# CANreader-FT.net
KiCad netlist of a schematic drawn in EAGLE
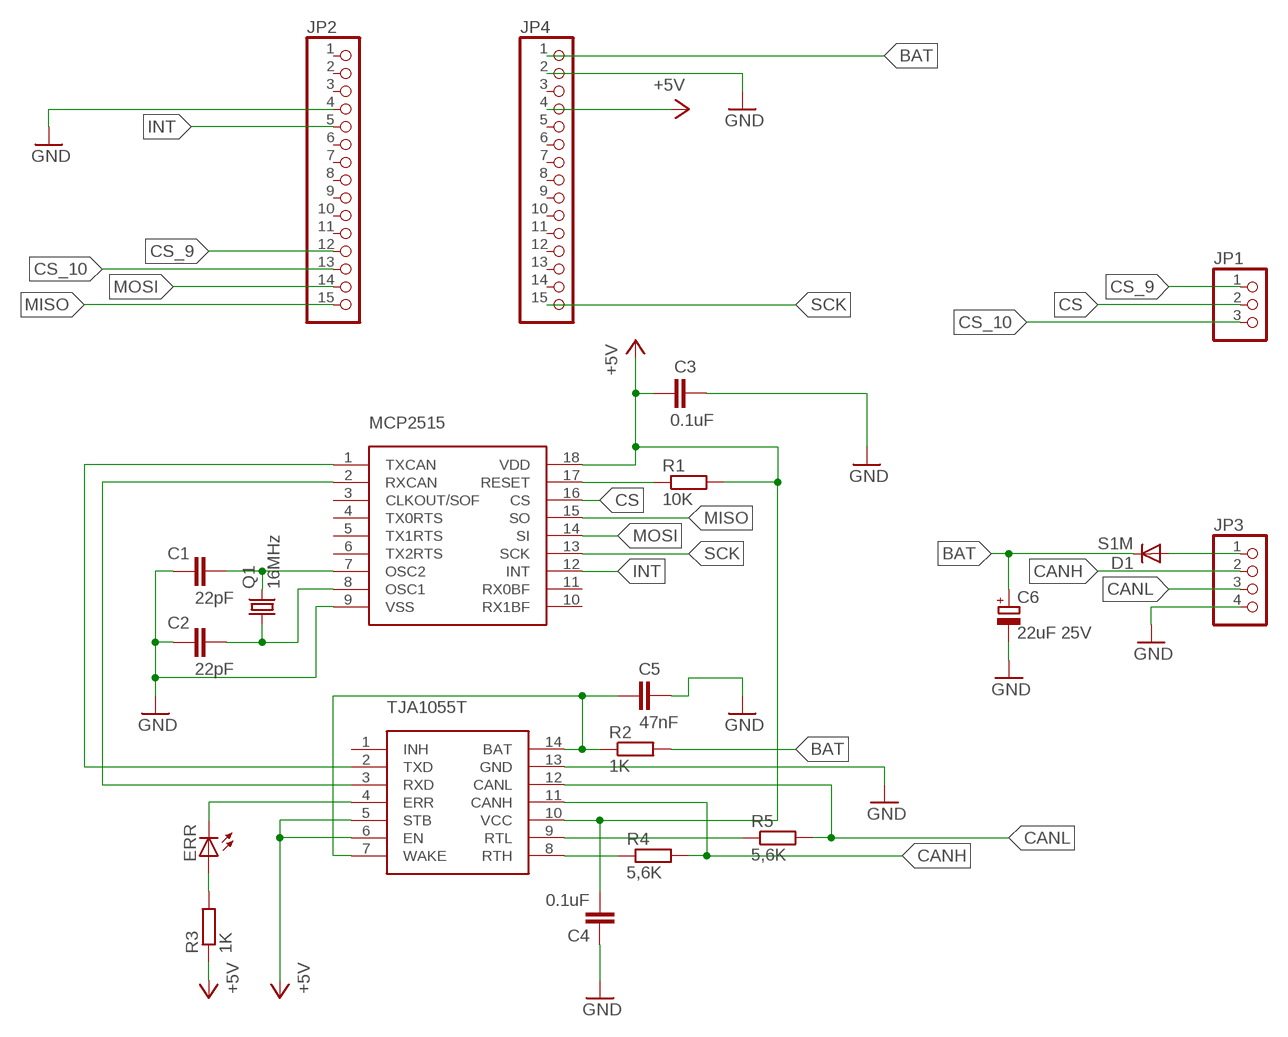
[diagram p0: schematic, sheet 1]

(export (version "E")
  (design (tool "Eeschema 10.0.6"))
  (components
    (comp (ref "C1")
      (value "22pF")
      (footprint "eagle-import:C0805")
      (libsource (lib "eagle-import") (part "C-EUC0805"))
    )
    (comp (ref "C2")
      (value "22pF")
      (footprint "eagle-import:C0805")
      (libsource (lib "eagle-import") (part "C-EUC0805"))
    )
    (comp (ref "C3")
      (value "0.1uF")
      (footprint "eagle-import:C0805")
      (libsource (lib "eagle-import") (part "C-EUC0805"))
    )
    (comp (ref "C4")
      (value "0.1uF")
      (footprint "eagle-import:C0805")
      (libsource (lib "eagle-import") (part "C-EUC0805"))
    )
    (comp (ref "C5")
      (value "47nF")
      (footprint "eagle-import:C0805")
      (libsource (lib "eagle-import") (part "C-EUC0805"))
    )
    (comp (ref "C6")
      (value "22uF 25V")
      (footprint "eagle-import:SMC_C")
      (libsource (lib "eagle-import") (part "CPOL-EUSMCC"))
    )
    (comp (ref "D1")
      (value "S1M")
      (footprint "eagle-import:SMA")
      (libsource (lib "eagle-import") (part "S1M"))
    )
    (comp (ref "ERR")
      (value "LEDCHIP-LED0805")
      (footprint "eagle-import:CHIP-LED0805")
      (libsource (lib "eagle-import") (part "LEDCHIP-LED0805"))
    )
    (comp (ref "JP1")
      (value "PINHD-1X3")
      (footprint "eagle-import:1X03")
      (libsource (lib "eagle-import") (part "PINHD-1X3"))
    )
    (comp (ref "JP2")
      (value "PINHD-1X15")
      (footprint "eagle-import:1X15")
      (libsource (lib "eagle-import") (part "PINHD-1X15"))
    )
    (comp (ref "JP3")
      (value "PINHD-1X4-1")
      (footprint "eagle-import:1X04")
      (libsource (lib "eagle-import") (part "PINHD-1X4-1"))
    )
    (comp (ref "JP4")
      (value "PINHD-1X15")
      (footprint "eagle-import:1X15")
      (libsource (lib "eagle-import") (part "PINHD-1X15"))
    )
    (comp (ref "MCP2515")
      (value "MCP2515")
      (footprint "eagle-import:SO18-1")
      (libsource (lib "eagle-import") (part "MCP2515"))
    )
    (comp (ref "Q1")
      (value "16MHz")
      (footprint "eagle-import:HC49_S")
      (libsource (lib "eagle-import") (part "CRYSTALHC49S"))
    )
    (comp (ref "R1")
      (value "10K")
      (footprint "eagle-import:R0805")
      (libsource (lib "eagle-import") (part "R-EU_R0805"))
    )
    (comp (ref "R2")
      (value "1K")
      (footprint "eagle-import:R0805")
      (libsource (lib "eagle-import") (part "R-EU_R0805"))
    )
    (comp (ref "R3")
      (value "1K")
      (footprint "eagle-import:R0805")
      (libsource (lib "eagle-import") (part "R-EU_R0805"))
    )
    (comp (ref "R4")
      (value "5,6K")
      (footprint "eagle-import:R0805")
      (libsource (lib "eagle-import") (part "R-EU_R0805"))
    )
    (comp (ref "R5")
      (value "5,6K")
      (footprint "eagle-import:R0805")
      (libsource (lib "eagle-import") (part "R-EU_R0805"))
    )
    (comp (ref "TJA1055T")
      (value "TJA1055T")
      (footprint "eagle-import:SO-14W")
      (libsource (lib "eagle-import") (part "TJA1055T"))
    )
  )
  (nets
    (net (code "1") (name "+5V") (class "Default")
      (node (ref "C3") (pin "1") (pinfunction "1_1") (pintype "passive"))
      (node (ref "C4") (pin "2") (pinfunction "2_2") (pintype "passive"))
      (node (ref "JP4") (pin "4") (pinfunction "4_4") (pintype "passive"))
      (node (ref "MCP2515") (pin "18") (pinfunction "VDD_18") (pintype "power_in"))
      (node (ref "R1") (pin "2") (pinfunction "2_2") (pintype "passive"))
      (node (ref "R3") (pin "1") (pinfunction "1_1") (pintype "passive"))
      (node (ref "TJA1055T") (pin "10") (pinfunction "VCC_10") (pintype "power_in"))
      (node (ref "TJA1055T") (pin "5") (pinfunction "STB_5") (pintype "input"))
      (node (ref "TJA1055T") (pin "6") (pinfunction "EN_6") (pintype "input"))
    )
    (net (code "2") (name "BAT") (class "Default")
      (node (ref "C6") (pin "+") (pinfunction "+_+") (pintype "passive"))
      (node (ref "D1") (pin "C") (pinfunction "C_C") (pintype "passive"))
      (node (ref "JP4") (pin "1") (pinfunction "1_1") (pintype "passive"))
      (node (ref "R2") (pin "2") (pinfunction "2_2") (pintype "passive"))
    )
    (net (code "3") (name "CANH") (class "Default")
      (node (ref "JP3") (pin "2") (pinfunction "2_2") (pintype "passive"))
      (node (ref "R4") (pin "2") (pinfunction "2_2") (pintype "passive"))
      (node (ref "TJA1055T") (pin "11") (pinfunction "CANH_11") (pintype "bidirectional"))
    )
    (net (code "4") (name "CANL") (class "Default")
      (node (ref "JP3") (pin "3") (pinfunction "3_3") (pintype "passive"))
      (node (ref "R5") (pin "2") (pinfunction "2_2") (pintype "passive"))
      (node (ref "TJA1055T") (pin "12") (pinfunction "CANL_12") (pintype "bidirectional"))
    )
    (net (code "5") (name "CS") (class "Default")
      (node (ref "JP1") (pin "2") (pinfunction "2_2") (pintype "passive"))
      (node (ref "MCP2515") (pin "16") (pinfunction "CS_16") (pintype "bidirectional"))
    )
    (net (code "6") (name "CS_9") (class "Default")
      (node (ref "JP1") (pin "1") (pinfunction "1_1") (pintype "passive"))
      (node (ref "JP2") (pin "12") (pinfunction "12_12") (pintype "passive"))
    )
    (net (code "7") (name "CS_10") (class "Default")
      (node (ref "JP1") (pin "3") (pinfunction "3_3") (pintype "passive"))
      (node (ref "JP2") (pin "13") (pinfunction "13_13") (pintype "passive"))
    )
    (net (code "8") (name "GND") (class "Default")
      (node (ref "C1") (pin "1") (pinfunction "1_1") (pintype "passive"))
      (node (ref "C2") (pin "1") (pinfunction "1_1") (pintype "passive"))
      (node (ref "C3") (pin "2") (pinfunction "2_2") (pintype "passive"))
      (node (ref "C4") (pin "1") (pinfunction "1_1") (pintype "passive"))
      (node (ref "C5") (pin "2") (pinfunction "2_2") (pintype "passive"))
      (node (ref "C6") (pin "-") (pinfunction "-_-") (pintype "passive"))
      (node (ref "JP2") (pin "4") (pinfunction "4_4") (pintype "passive"))
      (node (ref "JP3") (pin "4") (pinfunction "4_4") (pintype "passive"))
      (node (ref "JP4") (pin "2") (pinfunction "2_2") (pintype "passive"))
      (node (ref "MCP2515") (pin "9") (pinfunction "VSS_9") (pintype "power_in"))
      (node (ref "TJA1055T") (pin "13") (pinfunction "GND_13") (pintype "power_in"))
    )
    (net (code "9") (name "INT") (class "Default")
      (node (ref "JP2") (pin "5") (pinfunction "5_5") (pintype "passive"))
      (node (ref "MCP2515") (pin "12") (pinfunction "INT_12") (pintype "bidirectional"))
    )
    (net (code "10") (name "MISO") (class "Default")
      (node (ref "JP2") (pin "15") (pinfunction "15_15") (pintype "passive"))
      (node (ref "MCP2515") (pin "15") (pinfunction "SO_15") (pintype "bidirectional"))
    )
    (net (code "11") (name "MOSI") (class "Default")
      (node (ref "JP2") (pin "14") (pinfunction "14_14") (pintype "passive"))
      (node (ref "MCP2515") (pin "14") (pinfunction "SI_14") (pintype "bidirectional"))
    )
    (net (code "12") (name "Net-(D1-PadA)") (class "Default")
      (node (ref "D1") (pin "A") (pinfunction "A_A") (pintype "passive"))
      (node (ref "JP3") (pin "1") (pinfunction "1_1") (pintype "passive"))
    )
    (net (code "13") (name "Net-(ERR-PadA)") (class "Default")
      (node (ref "ERR") (pin "A") (pinfunction "A_A") (pintype "passive"))
      (node (ref "R3") (pin "2") (pinfunction "2_2") (pintype "passive"))
    )
    (net (code "14") (name "Net-(MCP2515-OSC1)") (class "Default")
      (node (ref "C2") (pin "2") (pinfunction "2_2") (pintype "passive"))
      (node (ref "MCP2515") (pin "8") (pinfunction "OSC1_8") (pintype "bidirectional"))
      (node (ref "Q1") (pin "1") (pinfunction "1_1") (pintype "passive"))
    )
    (net (code "15") (name "Net-(MCP2515-OSC2)") (class "Default")
      (node (ref "C1") (pin "2") (pinfunction "2_2") (pintype "passive"))
      (node (ref "MCP2515") (pin "7") (pinfunction "OSC2_7") (pintype "bidirectional"))
      (node (ref "Q1") (pin "2") (pinfunction "2_2") (pintype "passive"))
    )
    (net (code "16") (name "Net-(MCP2515-RESET)") (class "Default")
      (node (ref "MCP2515") (pin "17") (pinfunction "RESET_17") (pintype "bidirectional"))
      (node (ref "R1") (pin "1") (pinfunction "1_1") (pintype "passive"))
    )
    (net (code "17") (name "Net-(MCP2515-RXCAN)") (class "Default")
      (node (ref "MCP2515") (pin "2") (pinfunction "RXCAN_2") (pintype "bidirectional"))
      (node (ref "TJA1055T") (pin "3") (pinfunction "RXD_3") (pintype "bidirectional"))
    )
    (net (code "18") (name "Net-(MCP2515-TXCAN)") (class "Default")
      (node (ref "MCP2515") (pin "1") (pinfunction "TXCAN_1") (pintype "bidirectional"))
      (node (ref "TJA1055T") (pin "2") (pinfunction "TXD_2") (pintype "bidirectional"))
    )
    (net (code "19") (name "Net-(TJA1055T-BAT)") (class "Default")
      (node (ref "C5") (pin "1") (pinfunction "1_1") (pintype "passive"))
      (node (ref "R2") (pin "1") (pinfunction "1_1") (pintype "passive"))
      (node (ref "TJA1055T") (pin "14") (pinfunction "BAT_14") (pintype "input"))
      (node (ref "TJA1055T") (pin "7") (pinfunction "WAKE_7") (pintype "input"))
    )
    (net (code "20") (name "Net-(TJA1055T-ERR)") (class "Default")
      (node (ref "ERR") (pin "C") (pinfunction "C_C") (pintype "passive"))
      (node (ref "TJA1055T") (pin "4") (pinfunction "ERR_4") (pintype "output"))
    )
    (net (code "21") (name "Net-(TJA1055T-RTH)") (class "Default")
      (node (ref "R4") (pin "1") (pinfunction "1_1") (pintype "passive"))
      (node (ref "TJA1055T") (pin "8") (pinfunction "RTH_8") (pintype "bidirectional"))
    )
    (net (code "22") (name "Net-(TJA1055T-RTL)") (class "Default")
      (node (ref "R5") (pin "1") (pinfunction "1_1") (pintype "passive"))
      (node (ref "TJA1055T") (pin "9") (pinfunction "RTL_9") (pintype "bidirectional"))
    )
    (net (code "23") (name "SCK") (class "Default")
      (node (ref "JP4") (pin "15") (pinfunction "15_15") (pintype "passive"))
      (node (ref "MCP2515") (pin "13") (pinfunction "SCK_13") (pintype "bidirectional"))
    )
    (net (code "24") (name "unconnected-(JP2-Pad1)") (class "Default")
      (node (ref "JP2") (pin "1") (pinfunction "1_1") (pintype "passive"))
    )
    (net (code "25") (name "unconnected-(JP2-Pad2)") (class "Default")
      (node (ref "JP2") (pin "2") (pinfunction "2_2") (pintype "passive"))
    )
    (net (code "26") (name "unconnected-(JP2-Pad3)") (class "Default")
      (node (ref "JP2") (pin "3") (pinfunction "3_3") (pintype "passive"))
    )
    (net (code "27") (name "unconnected-(JP2-Pad6)") (class "Default")
      (node (ref "JP2") (pin "6") (pinfunction "6_6") (pintype "passive"))
    )
    (net (code "28") (name "unconnected-(JP2-Pad7)") (class "Default")
      (node (ref "JP2") (pin "7") (pinfunction "7_7") (pintype "passive"))
    )
    (net (code "29") (name "unconnected-(JP2-Pad8)") (class "Default")
      (node (ref "JP2") (pin "8") (pinfunction "8_8") (pintype "passive"))
    )
    (net (code "30") (name "unconnected-(JP2-Pad9)") (class "Default")
      (node (ref "JP2") (pin "9") (pinfunction "9_9") (pintype "passive"))
    )
    (net (code "31") (name "unconnected-(JP2-Pad10)") (class "Default")
      (node (ref "JP2") (pin "10") (pinfunction "10_10") (pintype "passive"))
    )
    (net (code "32") (name "unconnected-(JP2-Pad11)") (class "Default")
      (node (ref "JP2") (pin "11") (pinfunction "11_11") (pintype "passive"))
    )
    (net (code "33") (name "unconnected-(JP4-Pad3)") (class "Default")
      (node (ref "JP4") (pin "3") (pinfunction "3_3") (pintype "passive"))
    )
    (net (code "34") (name "unconnected-(JP4-Pad5)") (class "Default")
      (node (ref "JP4") (pin "5") (pinfunction "5_5") (pintype "passive"))
    )
    (net (code "35") (name "unconnected-(JP4-Pad6)") (class "Default")
      (node (ref "JP4") (pin "6") (pinfunction "6_6") (pintype "passive"))
    )
    (net (code "36") (name "unconnected-(JP4-Pad7)") (class "Default")
      (node (ref "JP4") (pin "7") (pinfunction "7_7") (pintype "passive"))
    )
    (net (code "37") (name "unconnected-(JP4-Pad8)") (class "Default")
      (node (ref "JP4") (pin "8") (pinfunction "8_8") (pintype "passive"))
    )
    (net (code "38") (name "unconnected-(JP4-Pad9)") (class "Default")
      (node (ref "JP4") (pin "9") (pinfunction "9_9") (pintype "passive"))
    )
    (net (code "39") (name "unconnected-(JP4-Pad10)") (class "Default")
      (node (ref "JP4") (pin "10") (pinfunction "10_10") (pintype "passive"))
    )
    (net (code "40") (name "unconnected-(JP4-Pad11)") (class "Default")
      (node (ref "JP4") (pin "11") (pinfunction "11_11") (pintype "passive"))
    )
    (net (code "41") (name "unconnected-(JP4-Pad12)") (class "Default")
      (node (ref "JP4") (pin "12") (pinfunction "12_12") (pintype "passive"))
    )
    (net (code "42") (name "unconnected-(JP4-Pad13)") (class "Default")
      (node (ref "JP4") (pin "13") (pinfunction "13_13") (pintype "passive"))
    )
    (net (code "43") (name "unconnected-(JP4-Pad14)") (class "Default")
      (node (ref "JP4") (pin "14") (pinfunction "14_14") (pintype "passive"))
    )
    (net (code "44") (name "unconnected-(MCP2515-CLKOUT{slash}SOF-Pad3)") (class "Default")
      (node (ref "MCP2515") (pin "3") (pinfunction "CLKOUT/SOF_3") (pintype "bidirectional"))
    )
    (net (code "45") (name "unconnected-(MCP2515-RX0BF-Pad11)") (class "Default")
      (node (ref "MCP2515") (pin "11") (pinfunction "RX0BF_11") (pintype "bidirectional"))
    )
    (net (code "46") (name "unconnected-(MCP2515-RX1BF-Pad10)") (class "Default")
      (node (ref "MCP2515") (pin "10") (pinfunction "RX1BF_10") (pintype "bidirectional"))
    )
    (net (code "47") (name "unconnected-(MCP2515-TX0RTS-Pad4)") (class "Default")
      (node (ref "MCP2515") (pin "4") (pinfunction "TX0RTS_4") (pintype "bidirectional"))
    )
    (net (code "48") (name "unconnected-(MCP2515-TX1RTS-Pad5)") (class "Default")
      (node (ref "MCP2515") (pin "5") (pinfunction "TX1RTS_5") (pintype "bidirectional"))
    )
    (net (code "49") (name "unconnected-(MCP2515-TX2RTS-Pad6)") (class "Default")
      (node (ref "MCP2515") (pin "6") (pinfunction "TX2RTS_6") (pintype "bidirectional"))
    )
    (net (code "50") (name "unconnected-(TJA1055T-INH-Pad1)") (class "Default")
      (node (ref "TJA1055T") (pin "1") (pinfunction "INH_1") (pintype "output"))
    )
  )
)
